# LISC_CPLD.net
KiCad netlist of a schematic drawn in Altium Designer
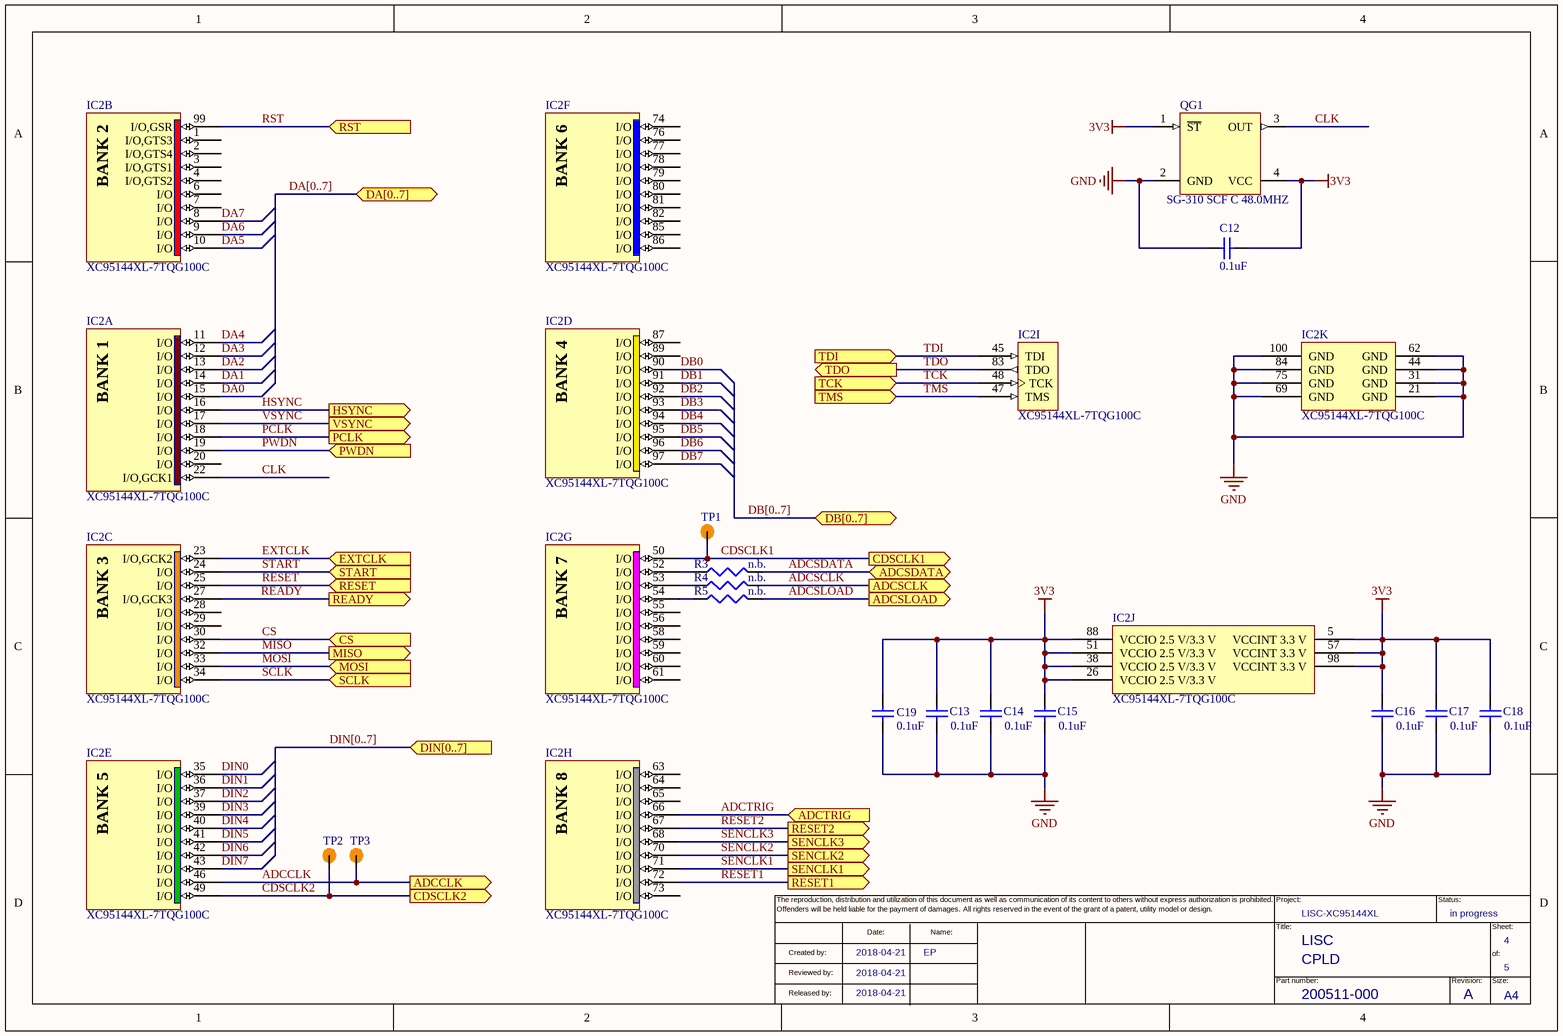
[diagram p0: LISC_CPLD.SchDoc]

(export (version "E")
  (design (tool "Eeschema 10.0.6"))
  (components
    (comp (ref "C12")
      (value "0.1uF")
      (footprint "1608[0603]")
      (description "Capacitor (Semiconductor SIM Model)")
      (fields (field (name "Comment") "Cap Semi") (field (name "PUBLISHER") "Altium Limited"))
      (libsource (lib "Miscellaneous Devices") (part "Cap Semi"))
    )
    (comp (ref "C13")
      (value "0.1uF")
      (footprint "1608[0603]")
      (description "Capacitor (Semiconductor SIM Model)")
      (fields (field (name "PUBLISHER") "Altium Limited"))
      (libsource (lib "Miscellaneous Devices") (part "Cap Semi"))
    )
    (comp (ref "C14")
      (value "0.1uF")
      (footprint "1608[0603]")
      (description "Capacitor (Semiconductor SIM Model)")
      (fields (field (name "PUBLISHER") "Altium Limited"))
      (libsource (lib "Miscellaneous Devices") (part "Cap Semi"))
    )
    (comp (ref "C15")
      (value "0.1uF")
      (footprint "1608[0603]")
      (description "Capacitor (Semiconductor SIM Model)")
      (fields (field (name "PUBLISHER") "Altium Limited"))
      (libsource (lib "Miscellaneous Devices") (part "Cap Semi"))
    )
    (comp (ref "C16")
      (value "0.1uF")
      (footprint "1608[0603]")
      (description "Capacitor (Semiconductor SIM Model)")
      (fields (field (name "PUBLISHER") "Altium Limited"))
      (libsource (lib "Miscellaneous Devices") (part "Cap Semi"))
    )
    (comp (ref "C17")
      (value "0.1uF")
      (footprint "1608[0603]")
      (description "Capacitor (Semiconductor SIM Model)")
      (fields (field (name "PUBLISHER") "Altium Limited"))
      (libsource (lib "Miscellaneous Devices") (part "Cap Semi"))
    )
    (comp (ref "C18")
      (value "0.1uF")
      (footprint "1608[0603]")
      (description "Capacitor (Semiconductor SIM Model)")
      (fields (field (name "PUBLISHER") "Altium Limited"))
      (libsource (lib "Miscellaneous Devices") (part "Cap Semi"))
    )
    (comp (ref "C19")
      (value "0.1uF")
      (footprint "1608[0603]")
      (description "Capacitor (Semiconductor SIM Model)")
      (fields (field (name "PUBLISHER") "Altium Limited"))
      (libsource (lib "Miscellaneous Devices") (part "Cap Semi"))
    )
    (comp (ref "IC2")
      (value "XC95144XL-7TQG100C")
      (footprint "TQG100_N")
      (fields (field (name "PUBLISHER") "Altium Limited"))
      (libsource (lib "Xilinx PLD XC9500XL") (part "XC95144XL-7TQG100C"))
    )
    (comp (ref "QG1")
      (value "SG-310 SCF C 48.0MHZ")
      (footprint "SG-310_Series")
      (description "EPSON TOYOCOM - SG-310 SCF C 20.0MHZ - OSZILLATOR, SM 3,2X2,5MM 20,0MHZ")
      (fields
        (field (name "MANUFACTURER") "EPSON TOYOCOM")
        (field (name "MANUFACTURER PART NUMBER") "SG-310 SCF C 20.0MHZ")
      )
      (libsource (lib "OSCILLATOR_LT") (part "SG-310 SCF C 20.0MHZ"))
    )
    (comp (ref "R3")
      (value "n.b.")
      (footprint "J1-0603")
      (description "Resistor")
      (fields (field (name "PUBLISHER") "Altium Limited"))
      (libsource (lib "Miscellaneous Devices") (part "Res3"))
    )
    (comp (ref "R4")
      (value "n.b.")
      (footprint "J1-0603")
      (description "Resistor")
      (fields (field (name "PUBLISHER") "Altium Limited"))
      (libsource (lib "Miscellaneous Devices") (part "Res3"))
    )
    (comp (ref "R5")
      (value "n.b.")
      (footprint "J1-0603")
      (description "Resistor")
      (fields (field (name "PUBLISHER") "Altium Limited"))
      (libsource (lib "Miscellaneous Devices") (part "Res3"))
    )
    (comp (ref "TP1")
      (value "TP_SMD")
      (footprint "TP100_200_NS")
      (libsource (lib "LISC-XC95144XL") (part "TP_SMD"))
    )
    (comp (ref "TP2")
      (value "TP_SMD")
      (footprint "TP100_200_NS")
      (libsource (lib "LISC-XC95144XL") (part "TP_SMD"))
    )
    (comp (ref "TP3")
      (value "TP_SMD")
      (footprint "TP100_200_NS")
      (libsource (lib "LISC-XC95144XL") (part "TP_SMD"))
    )
  )
  (nets
    (net (code "1") (name "/ADCCLK") (class "Default")
      (node (ref "IC2") (pin "46") (pinfunction "I/O_46") (pintype "bidirectional"))
      (node (ref "TP3") (pin "1") (pintype "passive"))
    )
    (net (code "2") (name "/ADCSCLK") (class "Default")
      (node (ref "R4") (pin "2") (pinfunction "2_2") (pintype "passive"))
    )
    (net (code "3") (name "/ADCSDATA") (class "Default")
      (node (ref "R3") (pin "2") (pinfunction "2_2") (pintype "passive"))
    )
    (net (code "4") (name "/ADCSLOAD") (class "Default")
      (node (ref "R5") (pin "2") (pinfunction "2_2") (pintype "passive"))
    )
    (net (code "5") (name "/ADCTRIG") (class "Default")
      (node (ref "IC2") (pin "66") (pinfunction "I/O_66") (pintype "bidirectional"))
    )
    (net (code "6") (name "/CDSCLK1") (class "Default")
      (node (ref "IC2") (pin "50") (pinfunction "I/O_50") (pintype "bidirectional"))
      (node (ref "TP1") (pin "1") (pintype "passive"))
    )
    (net (code "7") (name "/CDSCLK2") (class "Default")
      (node (ref "IC2") (pin "49") (pinfunction "I/O_49") (pintype "bidirectional"))
      (node (ref "TP2") (pin "1") (pintype "passive"))
    )
    (net (code "8") (name "/CLK") (class "Default")
      (node (ref "IC2") (pin "22") (pinfunction "I/O,GCK1_22") (pintype "bidirectional"))
      (node (ref "QG1") (pin "3") (pinfunction "OUT_3") (pintype "output"))
    )
    (net (code "9") (name "/CS") (class "Default")
      (node (ref "IC2") (pin "30") (pinfunction "I/O_30") (pintype "bidirectional"))
    )
    (net (code "10") (name "/DA0") (class "Default")
      (node (ref "IC2") (pin "15") (pinfunction "I/O_15") (pintype "bidirectional"))
    )
    (net (code "11") (name "/DA1") (class "Default")
      (node (ref "IC2") (pin "14") (pinfunction "I/O_14") (pintype "bidirectional"))
    )
    (net (code "12") (name "/DA2") (class "Default")
      (node (ref "IC2") (pin "13") (pinfunction "I/O_13") (pintype "bidirectional"))
    )
    (net (code "13") (name "/DA3") (class "Default")
      (node (ref "IC2") (pin "12") (pinfunction "I/O_12") (pintype "bidirectional"))
    )
    (net (code "14") (name "/DA4") (class "Default")
      (node (ref "IC2") (pin "11") (pinfunction "I/O_11") (pintype "bidirectional"))
    )
    (net (code "15") (name "/DA5") (class "Default")
      (node (ref "IC2") (pin "10") (pinfunction "I/O_10") (pintype "bidirectional"))
    )
    (net (code "16") (name "/DA6") (class "Default")
      (node (ref "IC2") (pin "9") (pinfunction "I/O_9") (pintype "bidirectional"))
    )
    (net (code "17") (name "/DA7") (class "Default")
      (node (ref "IC2") (pin "8") (pinfunction "I/O_8") (pintype "bidirectional"))
    )
    (net (code "19") (name "/DB0") (class "Default")
      (node (ref "IC2") (pin "90") (pinfunction "I/O_90") (pintype "bidirectional"))
    )
    (net (code "20") (name "/DB1") (class "Default")
      (node (ref "IC2") (pin "91") (pinfunction "I/O_91") (pintype "bidirectional"))
    )
    (net (code "21") (name "/DB2") (class "Default")
      (node (ref "IC2") (pin "92") (pinfunction "I/O_92") (pintype "bidirectional"))
    )
    (net (code "22") (name "/DB3") (class "Default")
      (node (ref "IC2") (pin "93") (pinfunction "I/O_93") (pintype "bidirectional"))
    )
    (net (code "23") (name "/DB4") (class "Default")
      (node (ref "IC2") (pin "94") (pinfunction "I/O_94") (pintype "bidirectional"))
    )
    (net (code "24") (name "/DB5") (class "Default")
      (node (ref "IC2") (pin "95") (pinfunction "I/O_95") (pintype "bidirectional"))
    )
    (net (code "25") (name "/DB6") (class "Default")
      (node (ref "IC2") (pin "96") (pinfunction "I/O_96") (pintype "bidirectional"))
    )
    (net (code "26") (name "/DB7") (class "Default")
      (node (ref "IC2") (pin "97") (pinfunction "I/O_97") (pintype "bidirectional"))
    )
    (net (code "28") (name "/DIN0") (class "Default")
      (node (ref "IC2") (pin "35") (pinfunction "I/O_35") (pintype "bidirectional"))
    )
    (net (code "29") (name "/DIN1") (class "Default")
      (node (ref "IC2") (pin "36") (pinfunction "I/O_36") (pintype "bidirectional"))
    )
    (net (code "30") (name "/DIN2") (class "Default")
      (node (ref "IC2") (pin "37") (pinfunction "I/O_37") (pintype "bidirectional"))
    )
    (net (code "31") (name "/DIN3") (class "Default")
      (node (ref "IC2") (pin "39") (pinfunction "I/O_39") (pintype "bidirectional"))
    )
    (net (code "32") (name "/DIN4") (class "Default")
      (node (ref "IC2") (pin "40") (pinfunction "I/O_40") (pintype "bidirectional"))
    )
    (net (code "33") (name "/DIN5") (class "Default")
      (node (ref "IC2") (pin "41") (pinfunction "I/O_41") (pintype "bidirectional"))
    )
    (net (code "34") (name "/DIN6") (class "Default")
      (node (ref "IC2") (pin "42") (pinfunction "I/O_42") (pintype "bidirectional"))
    )
    (net (code "35") (name "/DIN7") (class "Default")
      (node (ref "IC2") (pin "43") (pinfunction "I/O_43") (pintype "bidirectional"))
    )
    (net (code "37") (name "/EXTCLK") (class "Default")
      (node (ref "IC2") (pin "23") (pinfunction "I/O,GCK2_23") (pintype "bidirectional"))
    )
    (net (code "38") (name "/HSYNC") (class "Default")
      (node (ref "IC2") (pin "16") (pinfunction "I/O_16") (pintype "bidirectional"))
    )
    (net (code "39") (name "/MISO") (class "Default")
      (node (ref "IC2") (pin "32") (pinfunction "I/O_32") (pintype "bidirectional"))
    )
    (net (code "40") (name "/MOSI") (class "Default")
      (node (ref "IC2") (pin "33") (pinfunction "I/O_33") (pintype "bidirectional"))
    )
    (net (code "41") (name "/PCLK") (class "Default")
      (node (ref "IC2") (pin "18") (pinfunction "I/O_18") (pintype "bidirectional"))
    )
    (net (code "42") (name "/PWDN") (class "Default")
      (node (ref "IC2") (pin "19") (pinfunction "I/O_19") (pintype "bidirectional"))
    )
    (net (code "43") (name "/READY") (class "Default")
      (node (ref "IC2") (pin "27") (pinfunction "I/O,GCK3_27") (pintype "bidirectional"))
    )
    (net (code "44") (name "/RESET") (class "Default")
      (node (ref "IC2") (pin "25") (pinfunction "I/O_25") (pintype "bidirectional"))
    )
    (net (code "45") (name "/RESET1") (class "Default")
      (node (ref "IC2") (pin "72") (pinfunction "I/O_72") (pintype "bidirectional"))
    )
    (net (code "46") (name "/RESET2") (class "Default")
      (node (ref "IC2") (pin "67") (pinfunction "I/O_67") (pintype "bidirectional"))
    )
    (net (code "47") (name "/RST") (class "Default")
      (node (ref "IC2") (pin "99") (pinfunction "I/O,GSR_99") (pintype "bidirectional"))
    )
    (net (code "48") (name "/SCLK") (class "Default")
      (node (ref "IC2") (pin "34") (pinfunction "I/O_34") (pintype "bidirectional"))
    )
    (net (code "49") (name "/SENCLK1") (class "Default")
      (node (ref "IC2") (pin "71") (pinfunction "I/O_71") (pintype "bidirectional"))
    )
    (net (code "50") (name "/SENCLK2") (class "Default")
      (node (ref "IC2") (pin "70") (pinfunction "I/O_70") (pintype "bidirectional"))
    )
    (net (code "51") (name "/SENCLK3") (class "Default")
      (node (ref "IC2") (pin "68") (pinfunction "I/O_68") (pintype "bidirectional"))
    )
    (net (code "52") (name "/START") (class "Default")
      (node (ref "IC2") (pin "24") (pinfunction "I/O_24") (pintype "bidirectional"))
    )
    (net (code "53") (name "/TCK") (class "Default")
      (node (ref "IC2") (pin "48") (pinfunction "TCK_48") (pintype "input"))
    )
    (net (code "54") (name "/TDI") (class "Default")
      (node (ref "IC2") (pin "45") (pinfunction "TDI_45") (pintype "input"))
    )
    (net (code "55") (name "/TDO") (class "Default")
      (node (ref "IC2") (pin "83") (pinfunction "TDO_83") (pintype "output"))
    )
    (net (code "56") (name "/TMS") (class "Default")
      (node (ref "IC2") (pin "47") (pinfunction "TMS_47") (pintype "input"))
    )
    (net (code "57") (name "/VSYNC") (class "Default")
      (node (ref "IC2") (pin "17") (pinfunction "I/O_17") (pintype "bidirectional"))
    )
    (net (code "58") (name "3V3") (class "Default")
      (node (ref "C12") (pin "2") (pinfunction "2_2") (pintype "passive"))
      (node (ref "C13") (pin "1") (pinfunction "1_1") (pintype "passive"))
      (node (ref "C14") (pin "1") (pinfunction "1_1") (pintype "passive"))
      (node (ref "C15") (pin "1") (pinfunction "1_1") (pintype "passive"))
      (node (ref "C16") (pin "1") (pinfunction "1_1") (pintype "passive"))
      (node (ref "C17") (pin "1") (pinfunction "1_1") (pintype "passive"))
      (node (ref "C18") (pin "1") (pinfunction "1_1") (pintype "passive"))
      (node (ref "C19") (pin "1") (pinfunction "1_1") (pintype "passive"))
      (node (ref "IC2") (pin "26") (pinfunction "VCCIO_2.5_V/3.3_V_26") (pintype "power_in"))
      (node (ref "IC2") (pin "38") (pinfunction "VCCIO_2.5_V/3.3_V_38") (pintype "power_in"))
      (node (ref "IC2") (pin "5") (pinfunction "VCCINT_3.3_V_5") (pintype "power_in"))
      (node (ref "IC2") (pin "51") (pinfunction "VCCIO_2.5_V/3.3_V_51") (pintype "power_in"))
      (node (ref "IC2") (pin "57") (pinfunction "VCCINT_3.3_V_57") (pintype "power_in"))
      (node (ref "IC2") (pin "88") (pinfunction "VCCIO_2.5_V/3.3_V_88") (pintype "power_in"))
      (node (ref "IC2") (pin "98") (pinfunction "VCCINT_3.3_V_98") (pintype "power_in"))
      (node (ref "QG1") (pin "1") (pinfunction "~{ST}_1") (pintype "input"))
      (node (ref "QG1") (pin "4") (pinfunction "VCC_4") (pintype "power_in"))
    )
    (net (code "59") (name "GND") (class "Default")
      (node (ref "C12") (pin "1") (pinfunction "1_1") (pintype "passive"))
      (node (ref "C13") (pin "2") (pinfunction "2_2") (pintype "passive"))
      (node (ref "C14") (pin "2") (pinfunction "2_2") (pintype "passive"))
      (node (ref "C15") (pin "2") (pinfunction "2_2") (pintype "passive"))
      (node (ref "C16") (pin "2") (pinfunction "2_2") (pintype "passive"))
      (node (ref "C17") (pin "2") (pinfunction "2_2") (pintype "passive"))
      (node (ref "C18") (pin "2") (pinfunction "2_2") (pintype "passive"))
      (node (ref "C19") (pin "2") (pinfunction "2_2") (pintype "passive"))
      (node (ref "IC2") (pin "100") (pinfunction "GND_100") (pintype "power_in"))
      (node (ref "IC2") (pin "21") (pinfunction "GND_21") (pintype "power_in"))
      (node (ref "IC2") (pin "31") (pinfunction "GND_31") (pintype "power_in"))
      (node (ref "IC2") (pin "44") (pinfunction "GND_44") (pintype "power_in"))
      (node (ref "IC2") (pin "62") (pinfunction "GND_62") (pintype "power_in"))
      (node (ref "IC2") (pin "69") (pinfunction "GND_69") (pintype "power_in"))
      (node (ref "IC2") (pin "75") (pinfunction "GND_75") (pintype "power_in"))
      (node (ref "IC2") (pin "84") (pinfunction "GND_84") (pintype "power_in"))
      (node (ref "QG1") (pin "2") (pinfunction "GND_2") (pintype "power_in"))
    )
    (net (code "60") (name "Net-(IC2G-I{slash}O-Pad52)") (class "Default")
      (node (ref "IC2") (pin "52") (pinfunction "I/O_52") (pintype "bidirectional"))
      (node (ref "R3") (pin "1") (pinfunction "1_1") (pintype "passive"))
    )
    (net (code "61") (name "Net-(IC2G-I{slash}O-Pad53)") (class "Default")
      (node (ref "IC2") (pin "53") (pinfunction "I/O_53") (pintype "bidirectional"))
      (node (ref "R4") (pin "1") (pinfunction "1_1") (pintype "passive"))
    )
    (net (code "62") (name "Net-(IC2G-I{slash}O-Pad54)") (class "Default")
      (node (ref "IC2") (pin "54") (pinfunction "I/O_54") (pintype "bidirectional"))
      (node (ref "R5") (pin "1") (pinfunction "1_1") (pintype "passive"))
    )
    (net (code "63") (name "unconnected-(IC2A-I{slash}O-Pad20)") (class "Default")
      (node (ref "IC2") (pin "20") (pinfunction "I/O_20") (pintype "bidirectional"))
    )
    (net (code "64") (name "unconnected-(IC2B-I{slash}O,GTS1-Pad3)") (class "Default")
      (node (ref "IC2") (pin "3") (pinfunction "I/O,GTS1_3") (pintype "bidirectional"))
    )
    (net (code "65") (name "unconnected-(IC2B-I{slash}O,GTS2-Pad4)") (class "Default")
      (node (ref "IC2") (pin "4") (pinfunction "I/O,GTS2_4") (pintype "bidirectional"))
    )
    (net (code "66") (name "unconnected-(IC2B-I{slash}O,GTS3-Pad1)") (class "Default")
      (node (ref "IC2") (pin "1") (pinfunction "I/O,GTS3_1") (pintype "bidirectional"))
    )
    (net (code "67") (name "unconnected-(IC2B-I{slash}O,GTS4-Pad2)") (class "Default")
      (node (ref "IC2") (pin "2") (pinfunction "I/O,GTS4_2") (pintype "bidirectional"))
    )
    (net (code "68") (name "unconnected-(IC2B-I{slash}O-Pad6)") (class "Default")
      (node (ref "IC2") (pin "6") (pinfunction "I/O_6") (pintype "bidirectional"))
    )
    (net (code "69") (name "unconnected-(IC2B-I{slash}O-Pad7)") (class "Default")
      (node (ref "IC2") (pin "7") (pinfunction "I/O_7") (pintype "bidirectional"))
    )
    (net (code "70") (name "unconnected-(IC2C-I{slash}O-Pad28)") (class "Default")
      (node (ref "IC2") (pin "28") (pinfunction "I/O_28") (pintype "bidirectional"))
    )
    (net (code "71") (name "unconnected-(IC2C-I{slash}O-Pad29)") (class "Default")
      (node (ref "IC2") (pin "29") (pinfunction "I/O_29") (pintype "bidirectional"))
    )
    (net (code "72") (name "unconnected-(IC2D-I{slash}O-Pad87)") (class "Default")
      (node (ref "IC2") (pin "87") (pinfunction "I/O_87") (pintype "bidirectional"))
    )
    (net (code "73") (name "unconnected-(IC2D-I{slash}O-Pad89)") (class "Default")
      (node (ref "IC2") (pin "89") (pinfunction "I/O_89") (pintype "bidirectional"))
    )
    (net (code "74") (name "unconnected-(IC2F-I{slash}O-Pad74)") (class "Default")
      (node (ref "IC2") (pin "74") (pinfunction "I/O_74") (pintype "bidirectional"))
    )
    (net (code "75") (name "unconnected-(IC2F-I{slash}O-Pad76)") (class "Default")
      (node (ref "IC2") (pin "76") (pinfunction "I/O_76") (pintype "bidirectional"))
    )
    (net (code "76") (name "unconnected-(IC2F-I{slash}O-Pad77)") (class "Default")
      (node (ref "IC2") (pin "77") (pinfunction "I/O_77") (pintype "bidirectional"))
    )
    (net (code "77") (name "unconnected-(IC2F-I{slash}O-Pad78)") (class "Default")
      (node (ref "IC2") (pin "78") (pinfunction "I/O_78") (pintype "bidirectional"))
    )
    (net (code "78") (name "unconnected-(IC2F-I{slash}O-Pad79)") (class "Default")
      (node (ref "IC2") (pin "79") (pinfunction "I/O_79") (pintype "bidirectional"))
    )
    (net (code "79") (name "unconnected-(IC2F-I{slash}O-Pad80)") (class "Default")
      (node (ref "IC2") (pin "80") (pinfunction "I/O_80") (pintype "bidirectional"))
    )
    (net (code "80") (name "unconnected-(IC2F-I{slash}O-Pad81)") (class "Default")
      (node (ref "IC2") (pin "81") (pinfunction "I/O_81") (pintype "bidirectional"))
    )
    (net (code "81") (name "unconnected-(IC2F-I{slash}O-Pad82)") (class "Default")
      (node (ref "IC2") (pin "82") (pinfunction "I/O_82") (pintype "bidirectional"))
    )
    (net (code "82") (name "unconnected-(IC2F-I{slash}O-Pad85)") (class "Default")
      (node (ref "IC2") (pin "85") (pinfunction "I/O_85") (pintype "bidirectional"))
    )
    (net (code "83") (name "unconnected-(IC2F-I{slash}O-Pad86)") (class "Default")
      (node (ref "IC2") (pin "86") (pinfunction "I/O_86") (pintype "bidirectional"))
    )
    (net (code "84") (name "unconnected-(IC2G-I{slash}O-Pad55)") (class "Default")
      (node (ref "IC2") (pin "55") (pinfunction "I/O_55") (pintype "bidirectional"))
    )
    (net (code "85") (name "unconnected-(IC2G-I{slash}O-Pad56)") (class "Default")
      (node (ref "IC2") (pin "56") (pinfunction "I/O_56") (pintype "bidirectional"))
    )
    (net (code "86") (name "unconnected-(IC2G-I{slash}O-Pad58)") (class "Default")
      (node (ref "IC2") (pin "58") (pinfunction "I/O_58") (pintype "bidirectional"))
    )
    (net (code "87") (name "unconnected-(IC2G-I{slash}O-Pad59)") (class "Default")
      (node (ref "IC2") (pin "59") (pinfunction "I/O_59") (pintype "bidirectional"))
    )
    (net (code "88") (name "unconnected-(IC2G-I{slash}O-Pad60)") (class "Default")
      (node (ref "IC2") (pin "60") (pinfunction "I/O_60") (pintype "bidirectional"))
    )
    (net (code "89") (name "unconnected-(IC2G-I{slash}O-Pad61)") (class "Default")
      (node (ref "IC2") (pin "61") (pinfunction "I/O_61") (pintype "bidirectional"))
    )
    (net (code "90") (name "unconnected-(IC2H-I{slash}O-Pad63)") (class "Default")
      (node (ref "IC2") (pin "63") (pinfunction "I/O_63") (pintype "bidirectional"))
    )
    (net (code "91") (name "unconnected-(IC2H-I{slash}O-Pad64)") (class "Default")
      (node (ref "IC2") (pin "64") (pinfunction "I/O_64") (pintype "bidirectional"))
    )
    (net (code "92") (name "unconnected-(IC2H-I{slash}O-Pad65)") (class "Default")
      (node (ref "IC2") (pin "65") (pinfunction "I/O_65") (pintype "bidirectional"))
    )
    (net (code "93") (name "unconnected-(IC2H-I{slash}O-Pad73)") (class "Default")
      (node (ref "IC2") (pin "73") (pinfunction "I/O_73") (pintype "bidirectional"))
    )
  )
)
